# Connector.net
KiCad netlist of a schematic drawn in Altium Designer
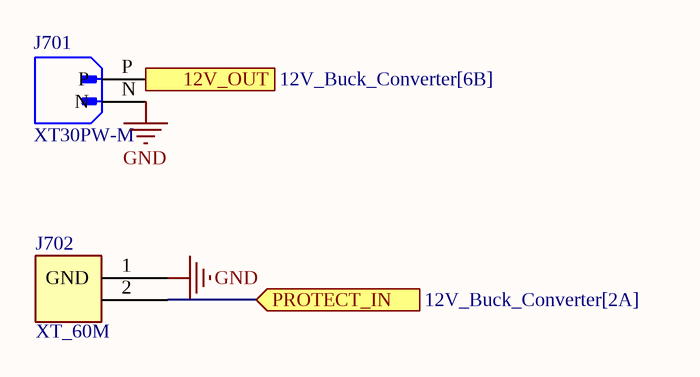
[diagram p0: Connector.SchDoc]

(export (version "E")
  (design (tool "Eeschema 10.0.6"))
  (components
    (comp (ref "J701")
      (value "XT30PW-M")
      (footprint "AMASS_XT30PW-M")
      (description "Socket; DC supply; XT30; male; PIN: 2; on PCBs; THT; Colour: yellow")
      (fields (field (name "MF") "AMASS"))
      (libsource (lib "robit circuit") (part "XT30PW-M"))
    )
    (comp (ref "J702")
      (value "XT_60M")
      (footprint "XT60_M")
      (description "XT_60 Connector MALE")
      (fields (field (name "SOURCE") "robit_connector.SchLib"))
      (libsource (lib "robit circuit") (part "XT_60M"))
    )
  )
  (nets
    (net (code "1") (name "/12V_OUT") (class "Default")
      (node (ref "J701") (pin "P") (pinfunction "P_P") (pintype "passive"))
    )
    (net (code "2") (name "/PROTECT_IN") (class "Default") (node (ref "J702") (pin "2") (pintype "passive")))
    (net (code "3") (name "GND") (class "Default")
      (node (ref "J701") (pin "N") (pinfunction "N_N") (pintype "power_in"))
      (node (ref "J702") (pin "1") (pinfunction "GND_1") (pintype "power_in"))
    )
  )
)
